# CAN.net
KiCad netlist of a schematic drawn in Altium Designer
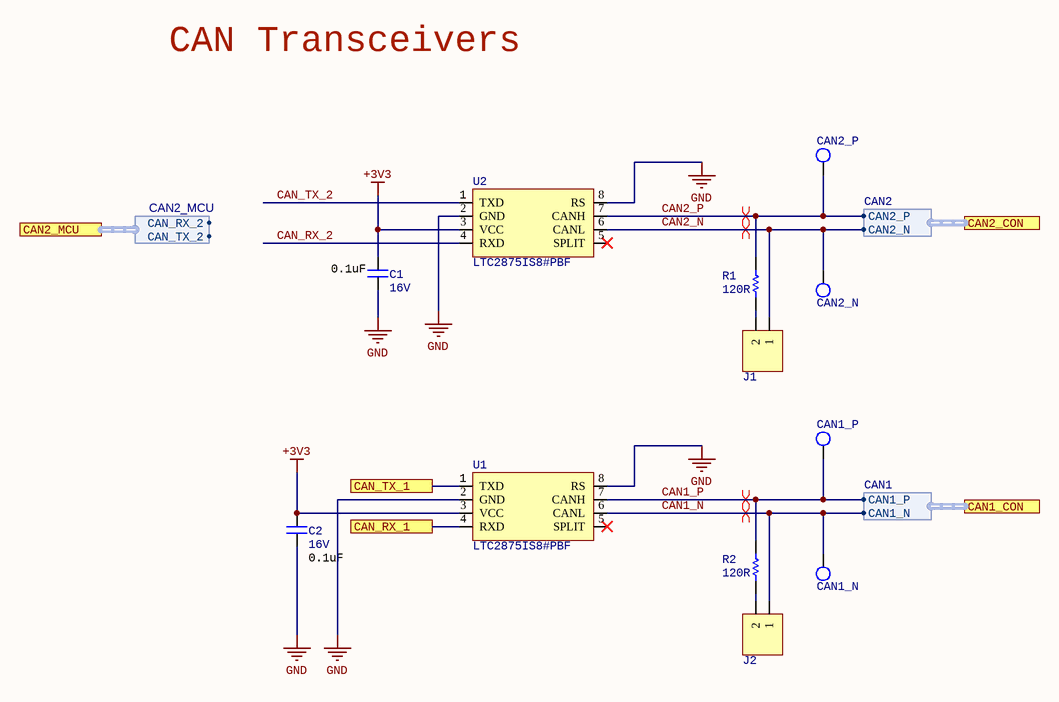
[diagram p0: CAN.SchDoc]

(export (version "E")
  (design (tool "Eeschema 10.0.6"))
  (components
    (comp (ref "C1")
      (value "0.1uF")
      (footprint "CAPC0603(1608)55_N")
      (description "CAP CER 0.1UF 16V X7R 0603")
      (fields
        (field (name "MPN") "CC0603KRX7R7BB104")
        (field (name "MANUFACTURER") "Yageo")
        (field (name "VOLTAGE RATING") "16V")
      )
      (libsource (lib "UWRT_Schematic_Library_2020") (part "CAP_0.1uF_16V_0603"))
    )
    (comp (ref "C2")
      (value "0.1uF")
      (footprint "CAPC0603(1608)55_N")
      (description "CAP CER 0.1UF 16V X7R 0603")
      (fields
        (field (name "MPN") "CC0603KRX7R7BB104")
        (field (name "MANUFACTURER") "Yageo")
        (field (name "VOLTAGE RATING") "16V")
      )
      (libsource (lib "UWRT_Schematic_Library_2020") (part "CAP_0.1uF_16V_0603"))
    )
    (comp (ref "CAN1_N")
      (value "TESTPOINT_LOOP")
      (footprint "TESTPOINT_LOOP")
      (description "Loop testpoint through-hole pad")
      (fields (field (name "MANUFACTURER") "Keystone Electronics"))
      (libsource (lib "UWRT_Schematic_Library_2020") (part "TESTPOINT_LOOP"))
    )
    (comp (ref "CAN1_P")
      (value "TESTPOINT_LOOP")
      (footprint "TESTPOINT_LOOP")
      (description "Loop testpoint through-hole pad")
      (fields (field (name "MANUFACTURER") "Keystone Electronics"))
      (libsource (lib "UWRT_Schematic_Library_2020") (part "TESTPOINT_LOOP"))
    )
    (comp (ref "CAN2_N")
      (value "TESTPOINT_LOOP")
      (footprint "TESTPOINT_LOOP")
      (description "Loop testpoint through-hole pad")
      (fields (field (name "MANUFACTURER") "Keystone Electronics"))
      (libsource (lib "UWRT_Schematic_Library_2020") (part "TESTPOINT_LOOP"))
    )
    (comp (ref "CAN2_P")
      (value "TESTPOINT_LOOP")
      (footprint "TESTPOINT_LOOP")
      (description "Loop testpoint through-hole pad")
      (fields (field (name "MANUFACTURER") "Keystone Electronics"))
      (libsource (lib "UWRT_Schematic_Library_2020") (part "TESTPOINT_LOOP"))
    )
    (comp (ref "J1")
      (value "JUMPER_2")
      (footprint "HDR1X2")
      (description "HEADER 2X1")
      (libsource (lib "UWRT_Schematic_Library_2020") (part "JUMPER_2"))
    )
    (comp (ref "J2")
      (value "JUMPER_2")
      (footprint "HDR1X2")
      (description "HEADER 2X1")
      (libsource (lib "UWRT_Schematic_Library_2020") (part "JUMPER_2"))
    )
    (comp (ref "R1")
      (value "120R")
      (footprint "RESC0603(1608)_N")
      (description "RES SMD 120 OHM 5% 1/10W 0603")
      (fields (field (name "MANUFACTURER") "Yageo") (field (name "MPN") "RC0603JR-07120RL"))
      (libsource (lib "UWRT_Schematic_Library_2020") (part "RES_120R_0603"))
    )
    (comp (ref "R2")
      (value "120R")
      (footprint "RESC0603(1608)_N")
      (description "RES SMD 120 OHM 5% 1/10W 0603")
      (fields (field (name "MANUFACTURER") "Yageo") (field (name "MPN") "RC0603JR-07120RL"))
      (libsource (lib "UWRT_Schematic_Library_2020") (part "RES_120R_0603"))
    )
    (comp (ref "U1")
      (value "IC TXRX CAN")
      (footprint "LT-S8_N")
      (description "IC TXRX CAN 4MBPS 8SO")
      (fields (field (name "MANUFACTURER") "Linear Technologies") (field (name "MPN") "LTC2875IS8#PBF"))
      (libsource (lib "UWRT_Schematic_Library_2020") (part "LTC2875"))
    )
    (comp (ref "U2")
      (value "IC TXRX CAN")
      (footprint "LT-S8_N")
      (description "IC TXRX CAN 4MBPS 8SO")
      (fields (field (name "MANUFACTURER") "Linear Technologies") (field (name "MPN") "LTC2875IS8#PBF"))
      (libsource (lib "UWRT_Schematic_Library_2020") (part "LTC2875"))
    )
  )
  (nets
    (net (code "4") (name "+3V3") (class "Default")
      (node (ref "C1") (pin "2") (pinfunction "2_2") (pintype "passive"))
      (node (ref "C2") (pin "2") (pinfunction "2_2") (pintype "passive"))
      (node (ref "U1") (pin "3") (pinfunction "VCC_3") (pintype "passive"))
      (node (ref "U2") (pin "3") (pinfunction "VCC_3") (pintype "passive"))
    )
    (net (code "5") (name "/CAN1_N") (class "Default")
      (node (ref "CAN1_N") (pin "1") (pintype "passive"))
      (node (ref "J2") (pin "1") (pinfunction "1_1") (pintype "passive"))
      (node (ref "U1") (pin "6") (pinfunction "CANL_6") (pintype "passive"))
    )
    (net (code "6") (name "/CAN1_P") (class "Default")
      (node (ref "CAN1_P") (pin "1") (pintype "passive"))
      (node (ref "R2") (pin "1") (pinfunction "1_1") (pintype "passive"))
      (node (ref "U1") (pin "7") (pinfunction "CANH_7") (pintype "passive"))
    )
    (net (code "7") (name "/CAN2_N") (class "Default")
      (node (ref "CAN2_N") (pin "1") (pintype "passive"))
      (node (ref "J1") (pin "1") (pinfunction "1_1") (pintype "passive"))
      (node (ref "U2") (pin "6") (pinfunction "CANL_6") (pintype "passive"))
    )
    (net (code "8") (name "/CAN2_P") (class "Default")
      (node (ref "CAN2_P") (pin "1") (pintype "passive"))
      (node (ref "R1") (pin "1") (pinfunction "1_1") (pintype "passive"))
      (node (ref "U2") (pin "7") (pinfunction "CANH_7") (pintype "passive"))
    )
    (net (code "9") (name "/CAN_RX_1") (class "Default")
      (node (ref "U1") (pin "4") (pinfunction "RXD_4") (pintype "passive"))
    )
    (net (code "10") (name "/CAN_RX_2") (class "Default")
      (node (ref "U2") (pin "4") (pinfunction "RXD_4") (pintype "passive"))
    )
    (net (code "11") (name "/CAN_TX_1") (class "Default")
      (node (ref "U1") (pin "1") (pinfunction "TXD_1") (pintype "passive"))
    )
    (net (code "12") (name "/CAN_TX_2") (class "Default")
      (node (ref "U2") (pin "1") (pinfunction "TXD_1") (pintype "passive"))
    )
    (net (code "16") (name "GND") (class "Default")
      (node (ref "C1") (pin "1") (pinfunction "1_1") (pintype "passive"))
      (node (ref "C2") (pin "1") (pinfunction "1_1") (pintype "passive"))
      (node (ref "U1") (pin "2") (pinfunction "GND_2") (pintype "passive"))
      (node (ref "U1") (pin "8") (pinfunction "RS_8") (pintype "passive"))
      (node (ref "U2") (pin "2") (pinfunction "GND_2") (pintype "passive"))
      (node (ref "U2") (pin "8") (pinfunction "RS_8") (pintype "passive"))
    )
    (net (code "17") (name "Net-(J1-Pad2)") (class "Default")
      (node (ref "J1") (pin "2") (pinfunction "2_2") (pintype "passive"))
      (node (ref "R1") (pin "2") (pinfunction "2_2") (pintype "passive"))
    )
    (net (code "18") (name "Net-(J2-Pad2)") (class "Default")
      (node (ref "J2") (pin "2") (pinfunction "2_2") (pintype "passive"))
      (node (ref "R2") (pin "2") (pinfunction "2_2") (pintype "passive"))
    )
    (net (code "19") (name "unconnected-(U1-SPLIT-Pad5)") (class "Default")
      (node (ref "U1") (pin "5") (pinfunction "SPLIT_5") (pintype "passive+no_connect"))
    )
    (net (code "20") (name "unconnected-(U2-SPLIT-Pad5)") (class "Default")
      (node (ref "U2") (pin "5") (pinfunction "SPLIT_5") (pintype "passive+no_connect"))
    )
  )
)
